# Power.net
KiCad netlist of a schematic drawn in Altium Designer
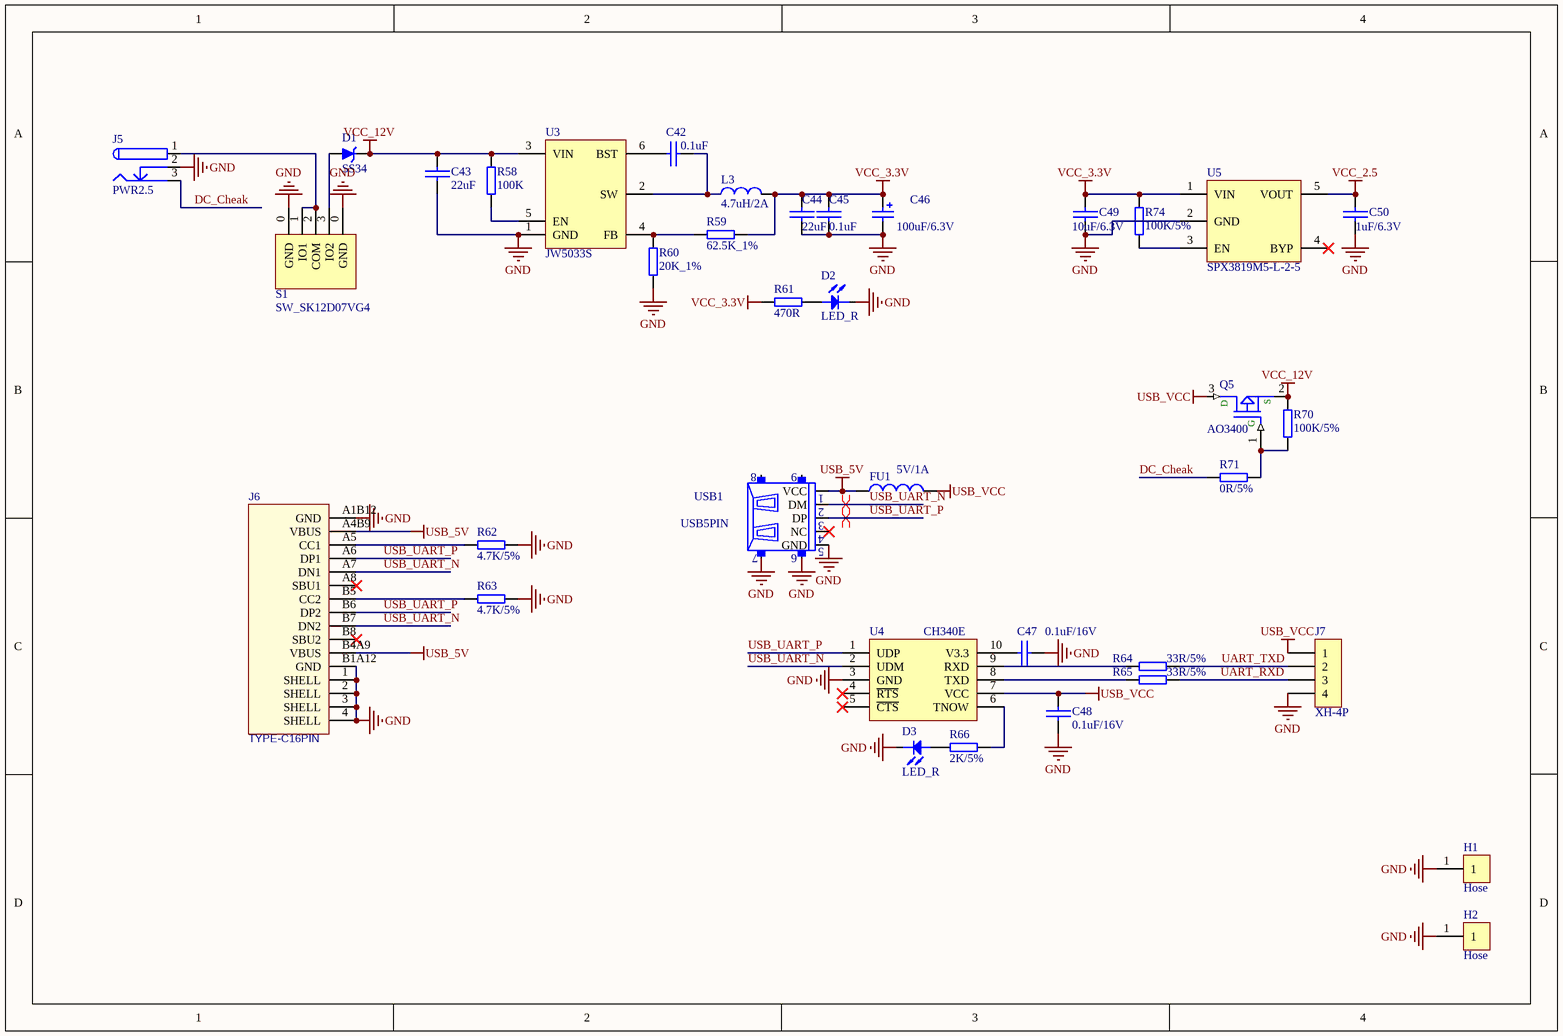
[diagram p0: Power.SchDoc]

(export (version "E")
  (design (tool "Eeschema 10.0.6"))
  (components
    (comp (ref "C42")
      (value "0.1uF")
      (footprint "0402C")
      (description "Capacitor")
      (libsource (lib "我的元件库_20180811") (part "CAP"))
    )
    (comp (ref "C43")
      (value "22uF")
      (footprint "0805C")
      (description "Capacitor")
      (libsource (lib "我的元件库_20180811") (part "CAP"))
    )
    (comp (ref "C44")
      (value "22uF")
      (footprint "0805C")
      (description "Capacitor")
      (libsource (lib "我的元件库_20180811") (part "CAP"))
    )
    (comp (ref "C45")
      (value "0.1uF")
      (footprint "0402C")
      (description "Capacitor")
      (libsource (lib "我的元件库_20180811") (part "CAP"))
    )
    (comp (ref "C46")
      (value "100uF/6.3V")
      (footprint "3528C")
      (description "插件电解电容")
      (fields (field (name "PUBLISHER") "Altium Limited"))
      (libsource (lib "*") (part "Cap Pol2"))
    )
    (comp (ref "C47")
      (value "0.1uF/16V")
      (footprint "0402C")
      (description "Capacitor")
      (libsource (lib "我的元件库_20180811") (part "CAP"))
    )
    (comp (ref "C48")
      (value "0.1uF/16V")
      (footprint "0402C")
      (description "Capacitor")
      (libsource (lib "我的元件库_20180811") (part "CAP"))
    )
    (comp (ref "C49")
      (value "10uF/6.3V")
      (footprint "0402C")
      (description "Capacitor")
      (libsource (lib "我的元件库_20180811") (part "CAP"))
    )
    (comp (ref "C50")
      (value "1uF/6.3V")
      (footprint "0402C")
      (description "Capacitor")
      (libsource (lib "我的元件库_20180811") (part "CAP"))
    )
    (comp (ref "D1") (value "SS34") (footprint "SMB") (libsource (lib "我的元件库") (part "DIODE_VZ")))
    (comp (ref "D2") (value "LED_R") (footprint "LED-0603") (libsource (lib "我的元件库") (part "LED")))
    (comp (ref "D3") (value "LED_R") (footprint "LED-0603") (libsource (lib "我的元件库_20180811") (part "LED")))
    (comp (ref "FU1")
      (value "5V/1A")
      (footprint "0603")
      (libsource (lib "我的元件库_20180811") (part "FB-90R-100Mhz"))
    )
    (comp (ref "H1") (value "Hose") (footprint "HOSE") (libsource (lib "我的元件库_20180811") (part "Hose")))
    (comp (ref "H2") (value "Hose") (footprint "HOSE") (libsource (lib "我的元件库_20180811") (part "Hose")))
    (comp (ref "J5")
      (value "PWR2.5")
      (footprint "pw2.5")
      (description "Low Voltage Power Supply Connector")
      (fields (field (name "PUBLISHER") "Altium Limited"))
      (libsource (lib "我的元件库") (part "PWR2.5"))
    )
    (comp (ref "J6")
      (value "TYPE-C16PIN")
      (footprint "USB-C-SMD_TYPE-C16PIN")
      (fields (field (name "BOM_SUPPLIER PART") "C393939") (field (name "CONTRIBUTOR") "LCSC"))
      (libsource (lib "我的元件库_20180811") (part "TYPE-C16PIN"))
    )
    (comp (ref "J7") (value "XH-4P") (footprint "DG1284") (libsource (lib "我的元件库") (part "CON4")))
    (comp (ref "L3")
      (value "4.7uH/2A")
      (footprint "CD54")
      (libsource (lib "我的元件库_20180811") (part "L-4.7uH-1206"))
    )
    (comp (ref "Q5") (value "AO3400") (footprint "SOT23") (libsource (lib "我的元件库_20180811") (part "MOS-P")))
    (comp (ref "R58") (value "100K") (footprint "0402R") (libsource (lib "我的元件库_20180811") (part "RES1")))
    (comp (ref "R59") (value "62.5K_1%") (footprint "0402R") (libsource (lib "我的元件库_20180811") (part "RES1")))
    (comp (ref "R60") (value "20K_1%") (footprint "0402R") (libsource (lib "我的元件库_20180811") (part "RES1")))
    (comp (ref "R61") (value "470R") (footprint "0402R") (libsource (lib "我的元件库_20180811") (part "RES1")))
    (comp (ref "R62") (value "4.7K/5%") (footprint "0402R") (libsource (lib "我的元件库_20180811") (part "RES1")))
    (comp (ref "R63") (value "4.7K/5%") (footprint "0402R") (libsource (lib "我的元件库_20180811") (part "RES1")))
    (comp (ref "R64") (value "33R/5%") (footprint "0402R") (libsource (lib "我的元件库_20180811") (part "RES1")))
    (comp (ref "R65") (value "33R/5%") (footprint "0402R") (libsource (lib "我的元件库_20180811") (part "RES1")))
    (comp (ref "R66") (value "2K/5%") (footprint "0402R") (libsource (lib "我的元件库_20180811") (part "RES1")))
    (comp (ref "R70") (value "100K/5%") (footprint "0402R") (libsource (lib "我的元件库_20180811") (part "RES1")))
    (comp (ref "R71") (value "0R/5%") (footprint "0402R") (libsource (lib "我的元件库_20180811") (part "RES1")))
    (comp (ref "R74") (value "100K/5%") (footprint "0402R") (libsource (lib "我的元件库_20180811") (part "RES1")))
    (comp (ref "S1")
      (value "SW_SK12D07VG4")
      (footprint "SW_SK12D07VG3")
      (libsource (lib "我的元件库_20180811") (part "SW_SK12D07VG4"))
    )
    (comp (ref "U3")
      (value "JW5033S")
      (footprint "SOT-23-6")
      (libsource (lib "我的元件库_20180811") (part "JW5033S"))
    )
    (comp (ref "U4") (value "CH340E") (footprint "MSOP10") (libsource (lib "我的元件库_20180811") (part "CH340E")))
    (comp (ref "U5")
      (value "SPX3819M5-L-2-5")
      (footprint "SOT-23-5")
      (libsource (lib "我的元件库_20180811") (part "SPX3819M5"))
    )
    (comp (ref "USB1") (value "USB5PIN") (footprint "MICROUSB") (libsource (lib "我的元件库") (part "USB-5PIN")))
  )
  (nets
    (net (code "1") (name "/DC_Cheak") (class "Default")
      (node (ref "J5") (pin "3") (pinfunction "3_3") (pintype "power_in"))
      (node (ref "R71") (pin "2") (pinfunction "2_2") (pintype "passive"))
    )
    (net (code "2") (name "/UART_RXD") (class "Default")
      (node (ref "J7") (pin "3") (pinfunction "3_3") (pintype "passive"))
      (node (ref "R65") (pin "1") (pinfunction "1_1") (pintype "passive"))
    )
    (net (code "3") (name "/UART_TXD") (class "Default")
      (node (ref "J7") (pin "2") (pinfunction "2_2") (pintype "passive"))
      (node (ref "R64") (pin "1") (pinfunction "1_1") (pintype "passive"))
    )
    (net (code "4") (name "/USB_UART_N") (class "Default")
      (node (ref "J6") (pin "A7") (pinfunction "DN1_A7") (pintype "passive"))
      (node (ref "J6") (pin "B7") (pinfunction "DN2_B7") (pintype "passive"))
      (node (ref "U4") (pin "2") (pinfunction "UDM_2") (pintype "passive"))
      (node (ref "USB1") (pin "2") (pinfunction "DM_2") (pintype "passive"))
    )
    (net (code "5") (name "/USB_UART_P") (class "Default")
      (node (ref "J6") (pin "A6") (pinfunction "DP1_A6") (pintype "passive"))
      (node (ref "J6") (pin "B6") (pinfunction "DP2_B6") (pintype "passive"))
      (node (ref "U4") (pin "1") (pinfunction "UDP_1") (pintype "passive"))
      (node (ref "USB1") (pin "3") (pinfunction "DP_3") (pintype "passive"))
    )
    (net (code "6") (name "GND") (class "Default")
      (node (ref "C43") (pin "2") (pinfunction "2_2") (pintype "passive"))
      (node (ref "C44") (pin "2") (pinfunction "2_2") (pintype "passive"))
      (node (ref "C45") (pin "1") (pinfunction "1_1") (pintype "passive"))
      (node (ref "C46") (pin "2") (pinfunction "2_2") (pintype "passive"))
      (node (ref "C47") (pin "2") (pinfunction "2_2") (pintype "passive"))
      (node (ref "C48") (pin "1") (pinfunction "1_1") (pintype "passive"))
      (node (ref "C49") (pin "2") (pinfunction "2_2") (pintype "passive"))
      (node (ref "C50") (pin "2") (pinfunction "2_2") (pintype "passive"))
      (node (ref "D2") (pin "2") (pinfunction "2_2") (pintype "passive"))
      (node (ref "D3") (pin "2") (pinfunction "2_2") (pintype "passive"))
      (node (ref "H1") (pin "1") (pinfunction "1_1") (pintype "passive"))
      (node (ref "H2") (pin "1") (pinfunction "1_1") (pintype "passive"))
      (node (ref "J5") (pin "2") (pinfunction "2_2") (pintype "power_in"))
      (node (ref "J6") (pin "1") (pinfunction "SHELL_1") (pintype "passive"))
      (node (ref "J6") (pin "2") (pinfunction "SHELL_2") (pintype "passive"))
      (node (ref "J6") (pin "3") (pinfunction "SHELL_3") (pintype "passive"))
      (node (ref "J6") (pin "4") (pinfunction "SHELL_4") (pintype "passive"))
      (node (ref "J6") (pin "A1B12") (pinfunction "GND_A1B12") (pintype "passive"))
      (node (ref "J6") (pin "B1A12") (pinfunction "GND_B1A12") (pintype "passive"))
      (node (ref "J7") (pin "4") (pinfunction "4_4") (pintype "passive"))
      (node (ref "R60") (pin "1") (pinfunction "1_1") (pintype "passive"))
      (node (ref "R62") (pin "1") (pinfunction "1_1") (pintype "passive"))
      (node (ref "R63") (pin "1") (pinfunction "1_1") (pintype "passive"))
      (node (ref "S1") (pin "0") (pinfunction "GND_0") (pintype "passive"))
      (node (ref "U3") (pin "1") (pinfunction "GND_1") (pintype "passive"))
      (node (ref "U4") (pin "3") (pinfunction "GND_3") (pintype "passive"))
      (node (ref "U5") (pin "2") (pinfunction "GND_2") (pintype "passive"))
      (node (ref "USB1") (pin "5") (pinfunction "GND_5") (pintype "passive"))
      (node (ref "USB1") (pin "6") (pinfunction "6_6") (pintype "passive"))
      (node (ref "USB1") (pin "7") (pinfunction "7_7") (pintype "passive"))
    )
    (net (code "7") (name "Net-(D2-Pad1)") (class "Default")
      (node (ref "D2") (pin "1") (pinfunction "1_1") (pintype "passive"))
      (node (ref "R61") (pin "2") (pinfunction "2_2") (pintype "passive"))
    )
    (net (code "8") (name "Net-(D3-Pad1)") (class "Default")
      (node (ref "D3") (pin "1") (pinfunction "1_1") (pintype "passive"))
      (node (ref "R66") (pin "1") (pinfunction "1_1") (pintype "passive"))
    )
    (net (code "9") (name "Net-(J6-CC1)") (class "Default")
      (node (ref "J6") (pin "A5") (pinfunction "CC1_A5") (pintype "passive"))
      (node (ref "R62") (pin "2") (pinfunction "2_2") (pintype "passive"))
    )
    (net (code "10") (name "Net-(J6-CC2)") (class "Default")
      (node (ref "J6") (pin "B5") (pinfunction "CC2_B5") (pintype "passive"))
      (node (ref "R63") (pin "2") (pinfunction "2_2") (pintype "passive"))
    )
    (net (code "11") (name "Net-(Q5-Pad1)") (class "Default")
      (node (ref "Q5") (pin "1") (pinfunction "1_1") (pintype "input"))
      (node (ref "R70") (pin "1") (pinfunction "1_1") (pintype "passive"))
      (node (ref "R71") (pin "1") (pinfunction "1_1") (pintype "passive"))
    )
    (net (code "12") (name "Net-(S1-COM)") (class "Default")
      (node (ref "J5") (pin "1") (pinfunction "1_1") (pintype "power_in"))
      (node (ref "S1") (pin "1") (pinfunction "IO1_1") (pintype "passive"))
      (node (ref "S1") (pin "2") (pinfunction "COM_2") (pintype "passive"))
    )
    (net (code "13") (name "Net-(S1-IO2)") (class "Default")
      (node (ref "D1") (pin "1") (pinfunction "1_1") (pintype "passive"))
      (node (ref "S1") (pin "3") (pinfunction "IO2_3") (pintype "passive"))
    )
    (net (code "14") (name "Net-(U3-BST)") (class "Default")
      (node (ref "C42") (pin "1") (pinfunction "1_1") (pintype "passive"))
      (node (ref "U3") (pin "6") (pinfunction "BST_6") (pintype "passive"))
    )
    (net (code "15") (name "Net-(U3-EN)") (class "Default")
      (node (ref "R58") (pin "2") (pinfunction "2_2") (pintype "passive"))
      (node (ref "U3") (pin "5") (pinfunction "EN_5") (pintype "passive"))
    )
    (net (code "16") (name "Net-(U3-FB)") (class "Default")
      (node (ref "R59") (pin "2") (pinfunction "2_2") (pintype "passive"))
      (node (ref "R60") (pin "2") (pinfunction "2_2") (pintype "passive"))
      (node (ref "U3") (pin "4") (pinfunction "FB_4") (pintype "passive"))
    )
    (net (code "17") (name "Net-(U3-SW)") (class "Default")
      (node (ref "C42") (pin "2") (pinfunction "2_2") (pintype "passive"))
      (node (ref "L3") (pin "2") (pinfunction "2_2") (pintype "passive"))
      (node (ref "U3") (pin "2") (pinfunction "SW_2") (pintype "passive"))
    )
    (net (code "18") (name "Net-(U4-RXD)") (class "Default")
      (node (ref "R64") (pin "2") (pinfunction "2_2") (pintype "passive"))
      (node (ref "U4") (pin "9") (pinfunction "RXD_9") (pintype "passive"))
    )
    (net (code "19") (name "Net-(U4-TNOW)") (class "Default")
      (node (ref "R66") (pin "2") (pinfunction "2_2") (pintype "passive"))
      (node (ref "U4") (pin "6") (pinfunction "TNOW_6") (pintype "passive"))
    )
    (net (code "20") (name "Net-(U4-TXD)") (class "Default")
      (node (ref "R65") (pin "2") (pinfunction "2_2") (pintype "passive"))
      (node (ref "U4") (pin "8") (pinfunction "TXD_8") (pintype "passive"))
    )
    (net (code "21") (name "Net-(U4-V3.3)") (class "Default")
      (node (ref "C47") (pin "1") (pinfunction "1_1") (pintype "passive"))
      (node (ref "U4") (pin "10") (pinfunction "V3.3_10") (pintype "passive"))
    )
    (net (code "22") (name "Net-(U5-EN)") (class "Default")
      (node (ref "R74") (pin "2") (pinfunction "2_2") (pintype "passive"))
      (node (ref "U5") (pin "3") (pinfunction "EN_3") (pintype "passive"))
    )
    (net (code "23") (name "USB_5V") (class "Default")
      (node (ref "FU1") (pin "1") (pinfunction "1_1") (pintype "passive"))
      (node (ref "J6") (pin "A4B9") (pinfunction "VBUS_A4B9") (pintype "passive"))
      (node (ref "J6") (pin "B4A9") (pinfunction "VBUS_B4A9") (pintype "passive"))
      (node (ref "USB1") (pin "1") (pinfunction "VCC_1") (pintype "passive"))
    )
    (net (code "24") (name "USB_VCC") (class "Default")
      (node (ref "C48") (pin "2") (pinfunction "2_2") (pintype "passive"))
      (node (ref "FU1") (pin "2") (pinfunction "2_2") (pintype "passive"))
      (node (ref "J7") (pin "1") (pinfunction "1_1") (pintype "passive"))
      (node (ref "Q5") (pin "3") (pinfunction "3_3") (pintype "input"))
      (node (ref "U4") (pin "7") (pinfunction "VCC_7") (pintype "passive"))
    )
    (net (code "25") (name "VCC_2.5") (class "Default")
      (node (ref "C50") (pin "1") (pinfunction "1_1") (pintype "passive"))
      (node (ref "U5") (pin "5") (pinfunction "VOUT_5") (pintype "passive"))
    )
    (net (code "26") (name "VCC_3.3V") (class "Default")
      (node (ref "C44") (pin "1") (pinfunction "1_1") (pintype "passive"))
      (node (ref "C45") (pin "2") (pinfunction "2_2") (pintype "passive"))
      (node (ref "C46") (pin "1") (pinfunction "1_1") (pintype "passive"))
      (node (ref "C49") (pin "1") (pinfunction "1_1") (pintype "passive"))
      (node (ref "L3") (pin "1") (pinfunction "1_1") (pintype "passive"))
      (node (ref "R59") (pin "1") (pinfunction "1_1") (pintype "passive"))
      (node (ref "R61") (pin "1") (pinfunction "1_1") (pintype "passive"))
      (node (ref "R74") (pin "1") (pinfunction "1_1") (pintype "passive"))
      (node (ref "U5") (pin "1") (pinfunction "VIN_1") (pintype "passive"))
    )
    (net (code "27") (name "VCC_12V") (class "Default")
      (node (ref "C43") (pin "1") (pinfunction "1_1") (pintype "passive"))
      (node (ref "D1") (pin "2") (pinfunction "2_2") (pintype "passive"))
      (node (ref "Q5") (pin "2") (pinfunction "2_2") (pintype "passive"))
      (node (ref "R58") (pin "1") (pinfunction "1_1") (pintype "passive"))
      (node (ref "R70") (pin "2") (pinfunction "2_2") (pintype "passive"))
      (node (ref "U3") (pin "3") (pinfunction "VIN_3") (pintype "passive"))
    )
    (net (code "28") (name "unconnected-(J6-SBU1-PadA8)") (class "Default")
      (node (ref "J6") (pin "A8") (pinfunction "SBU1_A8") (pintype "passive+no_connect"))
    )
    (net (code "29") (name "unconnected-(J6-SBU2-PadB8)") (class "Default")
      (node (ref "J6") (pin "B8") (pinfunction "SBU2_B8") (pintype "passive+no_connect"))
    )
    (net (code "30") (name "unconnected-(U4-~{CTS}-Pad5)") (class "Default")
      (node (ref "U4") (pin "5") (pinfunction "~{CTS}_5") (pintype "passive+no_connect"))
    )
    (net (code "31") (name "unconnected-(U4-~{RTS}-Pad4)") (class "Default")
      (node (ref "U4") (pin "4") (pinfunction "~{RTS}_4") (pintype "passive+no_connect"))
    )
    (net (code "32") (name "unconnected-(U5-BYP-Pad4)") (class "Default")
      (node (ref "U5") (pin "4") (pinfunction "BYP_4") (pintype "passive+no_connect"))
    )
    (net (code "33") (name "unconnected-(USB1-NC-Pad4)") (class "Default")
      (node (ref "USB1") (pin "4") (pinfunction "NC_4") (pintype "passive+no_connect"))
    )
    (net (code "34") (name "unconnected-(USB1-Pad8)") (class "Default")
      (node (ref "USB1") (pin "8") (pinfunction "8_8") (pintype "passive"))
    )
    (net (code "35") (name "unconnected-(USB1-Pad9)") (class "Default")
      (node (ref "USB1") (pin "9") (pinfunction "9_9") (pintype "passive"))
    )
  )
)
